# communication.net
KiCad netlist of a schematic drawn in Altium Designer
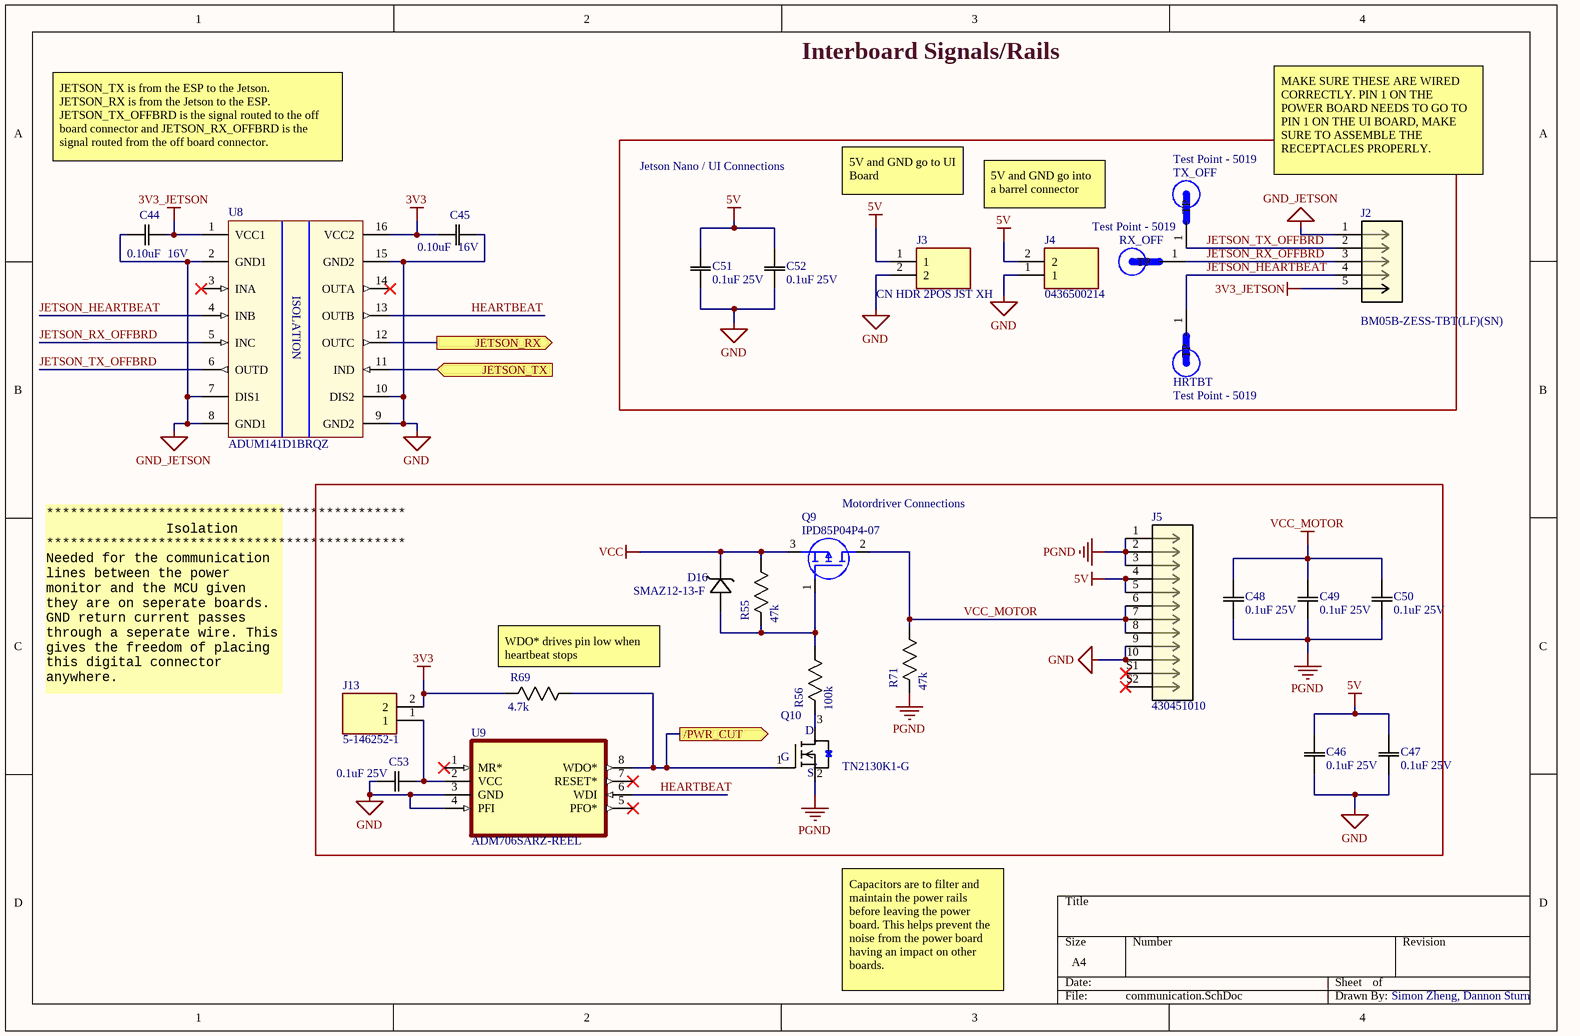
[diagram p0: communication.SchDoc]

(export (version "E")
  (design (tool "Eeschema 10.0.6"))
  (components
    (comp (ref "C44")
      (value "0.10uF")
      (footprint "0603")
      (description "CAP CER 0.10UF 16V X5R 0603/0805")
      (fields (field (name "TOLERANCE") "10%") (field (name "RATING") "16V"))
      (libsource (lib "AltiumLibraries") (part "CAP 0.10uF 16V"))
    )
    (comp (ref "C45")
      (value "0.10uF")
      (footprint "0603")
      (description "CAP CER 0.10UF 16V X5R 0603/0805")
      (fields (field (name "TOLERANCE") "10%") (field (name "RATING") "16V"))
      (libsource (lib "AltiumLibraries") (part "CAP 0.10uF 16V"))
    )
    (comp (ref "C46")
      (value "0.1uF 25V")
      (footprint "0603")
      (description "CAP CER 0.1UF 25V X7R 0805/0603")
      (fields (field (name "TOLERANCE") "10%"))
      (libsource (lib "AltiumLibraries") (part "CAP 0.1uF 25V"))
    )
    (comp (ref "C47")
      (value "0.1uF 25V")
      (footprint "0603")
      (description "CAP CER 0.1UF 25V X7R 0805/0603")
      (fields (field (name "TOLERANCE") "10%"))
      (libsource (lib "AltiumLibraries") (part "CAP 0.1uF 25V"))
    )
    (comp (ref "C48")
      (value "0.1uF 25V")
      (footprint "0603")
      (description "CAP CER 0.1UF 25V X7R 0805/0603")
      (fields (field (name "TOLERANCE") "10%"))
      (libsource (lib "AltiumLibraries") (part "CAP 0.1uF 25V"))
    )
    (comp (ref "C49")
      (value "0.1uF 25V")
      (footprint "0603")
      (description "CAP CER 0.1UF 25V X7R 0805/0603")
      (fields (field (name "TOLERANCE") "10%"))
      (libsource (lib "AltiumLibraries") (part "CAP 0.1uF 25V"))
    )
    (comp (ref "C50")
      (value "0.1uF 25V")
      (footprint "0603")
      (description "CAP CER 0.1UF 25V X7R 0805/0603")
      (fields (field (name "TOLERANCE") "10%"))
      (libsource (lib "AltiumLibraries") (part "CAP 0.1uF 25V"))
    )
    (comp (ref "C51")
      (value "0.1uF 25V")
      (footprint "0603")
      (description "CAP CER 0.1UF 25V X7R 0805/0603")
      (fields (field (name "TOLERANCE") "10%"))
      (libsource (lib "AltiumLibraries") (part "CAP 0.1uF 25V"))
    )
    (comp (ref "C52")
      (value "0.1uF 25V")
      (footprint "0603")
      (description "CAP CER 0.1UF 25V X7R 0805/0603")
      (fields (field (name "TOLERANCE") "10%"))
      (libsource (lib "AltiumLibraries") (part "CAP 0.1uF 25V"))
    )
    (comp (ref "C53")
      (value "0.1uF 25V")
      (footprint "0603")
      (description "CAP CER 0.1UF 25V X7R 0805/0603")
      (fields (field (name "TOLERANCE") "10%"))
      (libsource (lib "AltiumLibraries") (part "CAP 0.1uF 25V"))
    )
    (comp (ref "D16")
      (value "SMAZ12-13-F")
      (footprint "SMA_DIO-L")
      (description "Zener Diode 12 V 1 W ±5% Surface Mount SMA")
      (fields (field (name "COPYRIGHT") "Copyright (C) 2021 Ultra Librarian. All rights reserved."))
      (libsource (lib "AltiumLibraries") (part "DIODE ZENER 12V 1W"))
    )
    (comp (ref "HRTBT")
      (value "Test Point - 5019")
      (footprint "TP380X203")
      (description "PC Test Point, Miniature Phosphor Bronze, Silver Plating Surface Mount Mounting Type")
      (fields (field (name "MP") "5019") (field (name "MF") "Keystone Electronics"))
      (libsource (lib "AltiumLibraries") (part "Test Point - 5019"))
    )
    (comp (ref "J2")
      (value "BM05B-ZESS-TBT(LF)(SN)")
      (footprint "JST ZE SMT 5POS")
      (description "CONN HEADER VERT SMD 5POS ZE")
      (libsource (lib "AltiumLibraries") (part "CN 5POS JST ZE SMT"))
    )
    (comp (ref "J3")
      (value "CN HDR 2POS JST XH")
      (footprint "JST_B2B-XH-A(LF)(SN)")
      (description "Connector Header Through Hole 2 position 0.098 _2.50mm_\r\nJST XH")
      (fields (field (name "MP") "B2B-XH-A_LF__SN_") (field (name "MF") "JST Sales"))
      (libsource (lib "AltiumLibraries") (part "CN HDR 2POS JST XH"))
    )
    (comp (ref "J4")
      (value "0436500214")
      (footprint "43650-0214")
      (description "Connector Header Surface Mount, Right Angle 2 position 0.118\" (3.00mm)")
      (fields (field (name "MANUFACTURER_PART_NUMBER") "43650-0214"))
      (libsource (lib "AltiumLibraries") (part "CN HDR 2POS Molex 0436500214"))
    )
    (comp (ref "J5")
      (value "430451010")
      (footprint "CON_430451010_MOL")
      (description "Connector Header Surface Mount, Right Angle 10 position 0.118\" (3.00mm)")
      (fields (field (name "COPYRIGHT") "Copyright (C) 2021 Ultra Librarian. All rights reserved."))
      (libsource (lib "AltiumLibraries") (part "CN HDR 10POS MOLEX 430451010"))
    )
    (comp (ref "J13")
      (value "5-146252-1")
      (footprint "TE_5-146252-1")
      (description "2 Pin Jumper Male Pins")
      (libsource (lib "AltiumLibraries") (part "5-146252-1"))
    )
    (comp (ref "Q9")
      (value "IPD85P04P4-07")
      (footprint "DPAK (TO-252)")
      (description "P-Channel 40 V 85A (Tc) 88W (Tc) Surface Mount PG-TO252-3-313")
      (libsource (lib "AltiumLibraries") (part "MOSFET IPD85P04P4-07"))
    )
    (comp (ref "Q10")
      (value "TN2130K1-G")
      (footprint "SOT95P237X112-3N")
      (description "N-Channel 300 V 85mA (Tj) 360mW (Tc) Surface Mount TO-236AB (SOT23)")
      (fields (field (name "COPYRIGHT") "Copyright (C) 2021 Ultra Librarian. All rights reserved."))
      (libsource (lib "AltiumLibraries") (part "MOSFET N-CH TN2130K1-G"))
    )
    (comp (ref "R55")
      (value "47k")
      (footprint "0603")
      (description "RES SMD 47k OHM 5% 1/8W 0805")
      (fields (field (name "TOLERANCE") "5%"))
      (libsource (lib "AltiumLibraries") (part "RES 47k 1/8W - 5%"))
    )
    (comp (ref "R56")
      (value "100k")
      (footprint "0603")
      (description "RES SMD 100K OHM 5% 1/8W 0805/0603")
      (fields (field (name "TOLERANCE") "5%"))
      (libsource (lib "AltiumLibraries") (part "RES 100k 1/8W - 5%"))
    )
    (comp (ref "R69")
      (value "4.7k")
      (footprint "0603")
      (description "RES SMD 4.7k OHM 5% 1/8W 0805")
      (fields (field (name "TOLERANCE") "5%"))
      (libsource (lib "AltiumLibraries") (part "RES 4.7k 1/8W - 5%"))
    )
    (comp (ref "R71")
      (value "47k")
      (footprint "0603")
      (description "RES SMD 47k OHM 5% 1/8W 0805")
      (fields (field (name "TOLERANCE") "5%"))
      (libsource (lib "AltiumLibraries") (part "RES 47k 1/8W - 5%"))
    )
    (comp (ref "RX_OFF")
      (value "Test Point - 5019")
      (footprint "TP380X203")
      (description "PC Test Point, Miniature Phosphor Bronze, Silver Plating Surface Mount Mounting Type")
      (fields (field (name "MP") "5019") (field (name "MF") "Keystone Electronics"))
      (libsource (lib "AltiumLibraries") (part "Test Point - 5019"))
    )
    (comp (ref "TX_OFF")
      (value "Test Point - 5019")
      (footprint "TP380X203")
      (description "PC Test Point, Miniature Phosphor Bronze, Silver Plating Surface Mount Mounting Type")
      (fields (field (name "MP") "5019") (field (name "MF") "Keystone Electronics"))
      (libsource (lib "AltiumLibraries") (part "Test Point - 5019"))
    )
    (comp (ref "U8")
      (value "ADUM141D1BRQZ")
      (footprint "SOP64P600X175-16N")
      (description "Digital Isolator CMOS 4-CH 150Mbps 16-Pin QSOP T/R")
      (fields
        (field (name "MANUFACTURER") "Analog Devices")
        (field (name "MANUFACTURER PART NUMBER") "ADUM141D1BRQZ-RL7")
      )
      (libsource (lib "AltiumLibraries") (part "ISO ADUM141D1BRQZ"))
    )
    (comp (ref "U9")
      (value "ADM706SARZ-REEL")
      (footprint "SOIC127P600X175-8N")
      (description "Supervisor Push-Pull, Totem Pole 1 Channel 8-SOIC")
      (fields
        (field (name "DIGI-KEY_PART_NUMBER") "ADM706SARZ-REELCT-ND")
        (field (name "MF") "Analog Devices")
      )
      (libsource (lib "AltiumLibraries") (part "ADM706SARZ-REEL"))
    )
  )
  (nets
    (net (code "1") (name "/HEARTBEAT") (class "Default")
      (node (ref "U8") (pin "13") (pinfunction "OUTB_13") (pintype "output"))
      (node (ref "U9") (pin "6") (pinfunction "WDI_6") (pintype "input"))
    )
    (net (code "2") (name "/JETSON_HEARTBEAT") (class "Default")
      (node (ref "HRTBT") (pin "1") (pinfunction "TP_1") (pintype "passive"))
      (node (ref "J2") (pin "4") (pinfunction "4_4") (pintype "passive"))
      (node (ref "U8") (pin "4") (pinfunction "INB_4") (pintype "input"))
    )
    (net (code "3") (name "/JETSON_RX") (class "Default")
      (node (ref "U8") (pin "12") (pinfunction "OUTC_12") (pintype "output"))
    )
    (net (code "4") (name "/JETSON_RX_OFFBRD") (class "Default")
      (node (ref "J2") (pin "3") (pinfunction "3_3") (pintype "passive"))
      (node (ref "RX_OFF") (pin "1") (pinfunction "TP_1") (pintype "passive"))
      (node (ref "U8") (pin "5") (pinfunction "INC_5") (pintype "input"))
    )
    (net (code "5") (name "/JETSON_TX") (class "Default")
      (node (ref "U8") (pin "11") (pinfunction "IND_11") (pintype "input"))
    )
    (net (code "6") (name "/JETSON_TX_OFFBRD") (class "Default")
      (node (ref "J2") (pin "2") (pinfunction "2_2") (pintype "passive"))
      (node (ref "TX_OFF") (pin "1") (pinfunction "TP_1") (pintype "passive"))
      (node (ref "U8") (pin "6") (pinfunction "OUTD_6") (pintype "output"))
    )
    (net (code "7") (name "/{slash}PWR_CUT") (class "Default")
      (node (ref "Q10") (pin "1") (pinfunction "G_1") (pintype "passive"))
      (node (ref "R69") (pin "1") (pinfunction "R1_1") (pintype "passive"))
      (node (ref "U9") (pin "8") (pinfunction "WDO*_8") (pintype "output"))
    )
    (net (code "8") (name "3V3") (class "Default")
      (node (ref "C45") (pin "2") (pinfunction "C2_2") (pintype "passive"))
      (node (ref "J13") (pin "2") (pinfunction "2_2") (pintype "passive"))
      (node (ref "R69") (pin "2") (pinfunction "R2_2") (pintype "passive"))
      (node (ref "U8") (pin "16") (pinfunction "VCC2_16") (pintype "power_in"))
    )
    (net (code "9") (name "3V3_JETSON") (class "Default")
      (node (ref "C44") (pin "2") (pinfunction "C2_2") (pintype "passive"))
      (node (ref "J2") (pin "5") (pinfunction "5_5") (pintype "passive"))
      (node (ref "U8") (pin "1") (pinfunction "VCC1_1") (pintype "power_in"))
    )
    (net (code "10") (name "5V") (class "Default")
      (node (ref "C46") (pin "2") (pinfunction "C2_2") (pintype "passive"))
      (node (ref "C47") (pin "2") (pinfunction "C2_2") (pintype "passive"))
      (node (ref "C51") (pin "2") (pinfunction "C2_2") (pintype "passive"))
      (node (ref "C52") (pin "2") (pinfunction "C2_2") (pintype "passive"))
      (node (ref "J3") (pin "1") (pinfunction "1_1") (pintype "passive"))
      (node (ref "J4") (pin "2") (pinfunction "2_2") (pintype "passive"))
      (node (ref "J5") (pin "4") (pinfunction "4_4") (pintype "passive"))
      (node (ref "J5") (pin "5") (pinfunction "5_5") (pintype "passive"))
    )
    (net (code "11") (name "GND") (class "Default")
      (node (ref "C45") (pin "1") (pinfunction "C1_1") (pintype "passive"))
      (node (ref "C46") (pin "1") (pinfunction "C1_1") (pintype "passive"))
      (node (ref "C47") (pin "1") (pinfunction "C1_1") (pintype "passive"))
      (node (ref "C51") (pin "1") (pinfunction "C1_1") (pintype "passive"))
      (node (ref "C52") (pin "1") (pinfunction "C1_1") (pintype "passive"))
      (node (ref "C53") (pin "1") (pinfunction "C1_1") (pintype "passive"))
      (node (ref "J3") (pin "2") (pinfunction "2_2") (pintype "passive"))
      (node (ref "J4") (pin "1") (pinfunction "1_1") (pintype "passive"))
      (node (ref "J5") (pin "10") (pinfunction "10_10") (pintype "passive"))
      (node (ref "J5") (pin "9") (pinfunction "9_9") (pintype "passive"))
      (node (ref "U8") (pin "10") (pinfunction "DIS2_10") (pintype "passive"))
      (node (ref "U8") (pin "15") (pinfunction "GND2_15") (pintype "power_in"))
      (node (ref "U8") (pin "9") (pinfunction "GND2_9") (pintype "power_in"))
      (node (ref "U9") (pin "3") (pinfunction "GND_3") (pintype "passive"))
      (node (ref "U9") (pin "4") (pinfunction "PFI_4") (pintype "input"))
    )
    (net (code "12") (name "GND_JETSON") (class "Default")
      (node (ref "C44") (pin "1") (pinfunction "C1_1") (pintype "passive"))
      (node (ref "J2") (pin "1") (pinfunction "1_1") (pintype "passive"))
      (node (ref "U8") (pin "2") (pinfunction "GND1_2") (pintype "power_in"))
      (node (ref "U8") (pin "7") (pinfunction "DIS1_7") (pintype "passive"))
      (node (ref "U8") (pin "8") (pinfunction "GND1_8") (pintype "power_in"))
    )
    (net (code "13") (name "Net-(C53-C2)") (class "Default")
      (node (ref "C53") (pin "2") (pinfunction "C2_2") (pintype "passive"))
      (node (ref "J13") (pin "1") (pinfunction "1_1") (pintype "passive"))
      (node (ref "U9") (pin "2") (pinfunction "VCC_2") (pintype "power_in"))
    )
    (net (code "14") (name "Net-(Q9-G)") (class "Default")
      (node (ref "D16") (pin "2") (pinfunction "2_2") (pintype "passive"))
      (node (ref "Q9") (pin "1") (pinfunction "G_1") (pintype "passive"))
      (node (ref "R55") (pin "2") (pinfunction "R2_2") (pintype "passive"))
      (node (ref "R56") (pin "1") (pinfunction "R1_1") (pintype "passive"))
    )
    (net (code "15") (name "Net-(Q10-D)") (class "Default")
      (node (ref "Q10") (pin "3") (pinfunction "D_3") (pintype "passive"))
      (node (ref "R56") (pin "2") (pinfunction "R2_2") (pintype "passive"))
    )
    (net (code "16") (name "PGND") (class "Default")
      (node (ref "C48") (pin "1") (pinfunction "C1_1") (pintype "passive"))
      (node (ref "C49") (pin "1") (pinfunction "C1_1") (pintype "passive"))
      (node (ref "C50") (pin "1") (pinfunction "C1_1") (pintype "passive"))
      (node (ref "J5") (pin "1") (pinfunction "1_1") (pintype "passive"))
      (node (ref "J5") (pin "2") (pinfunction "2_2") (pintype "passive"))
      (node (ref "J5") (pin "3") (pinfunction "3_3") (pintype "passive"))
      (node (ref "Q10") (pin "2") (pinfunction "S_2") (pintype "passive"))
      (node (ref "R71") (pin "2") (pinfunction "R2_2") (pintype "passive"))
    )
    (net (code "17") (name "VCC") (class "Default")
      (node (ref "D16") (pin "1") (pinfunction "1_1") (pintype "passive"))
      (node (ref "Q9") (pin "3") (pinfunction "S_3") (pintype "passive"))
      (node (ref "R55") (pin "1") (pinfunction "R1_1") (pintype "passive"))
    )
    (net (code "18") (name "VCC_MOTOR") (class "Default")
      (node (ref "C48") (pin "2") (pinfunction "C2_2") (pintype "passive"))
      (node (ref "C49") (pin "2") (pinfunction "C2_2") (pintype "passive"))
      (node (ref "C50") (pin "2") (pinfunction "C2_2") (pintype "passive"))
      (node (ref "J5") (pin "6") (pinfunction "6_6") (pintype "passive"))
      (node (ref "J5") (pin "7") (pinfunction "7_7") (pintype "passive"))
      (node (ref "J5") (pin "8") (pinfunction "8_8") (pintype "passive"))
      (node (ref "Q9") (pin "2") (pinfunction "D_2") (pintype "passive"))
      (node (ref "R71") (pin "1") (pinfunction "R1_1") (pintype "passive"))
    )
    (net (code "19") (name "unconnected-(J5-PadS1)") (class "Default")
      (node (ref "J5") (pin "S1") (pinfunction "S1_S1") (pintype "passive+no_connect"))
    )
    (net (code "20") (name "unconnected-(J5-PadS2)") (class "Default")
      (node (ref "J5") (pin "S2") (pinfunction "S2_S2") (pintype "passive+no_connect"))
    )
    (net (code "21") (name "unconnected-(U8-INA-Pad3)") (class "Default")
      (node (ref "U8") (pin "3") (pinfunction "INA_3") (pintype "input+no_connect"))
    )
    (net (code "22") (name "unconnected-(U8-OUTA-Pad14)") (class "Default")
      (node (ref "U8") (pin "14") (pinfunction "OUTA_14") (pintype "output+no_connect"))
    )
    (net (code "23") (name "unconnected-(U9-MR*-Pad1)") (class "Default")
      (node (ref "U9") (pin "1") (pinfunction "MR*_1") (pintype "input+no_connect"))
    )
    (net (code "24") (name "unconnected-(U9-PFO*-Pad5)") (class "Default")
      (node (ref "U9") (pin "5") (pinfunction "PFO*_5") (pintype "output+no_connect"))
    )
    (net (code "25") (name "unconnected-(U9-RESET*-Pad7)") (class "Default")
      (node (ref "U9") (pin "7") (pinfunction "RESET*_7") (pintype "output+no_connect"))
    )
  )
)
